# Master.net
KiCad netlist of a schematic drawn in Altium Designer
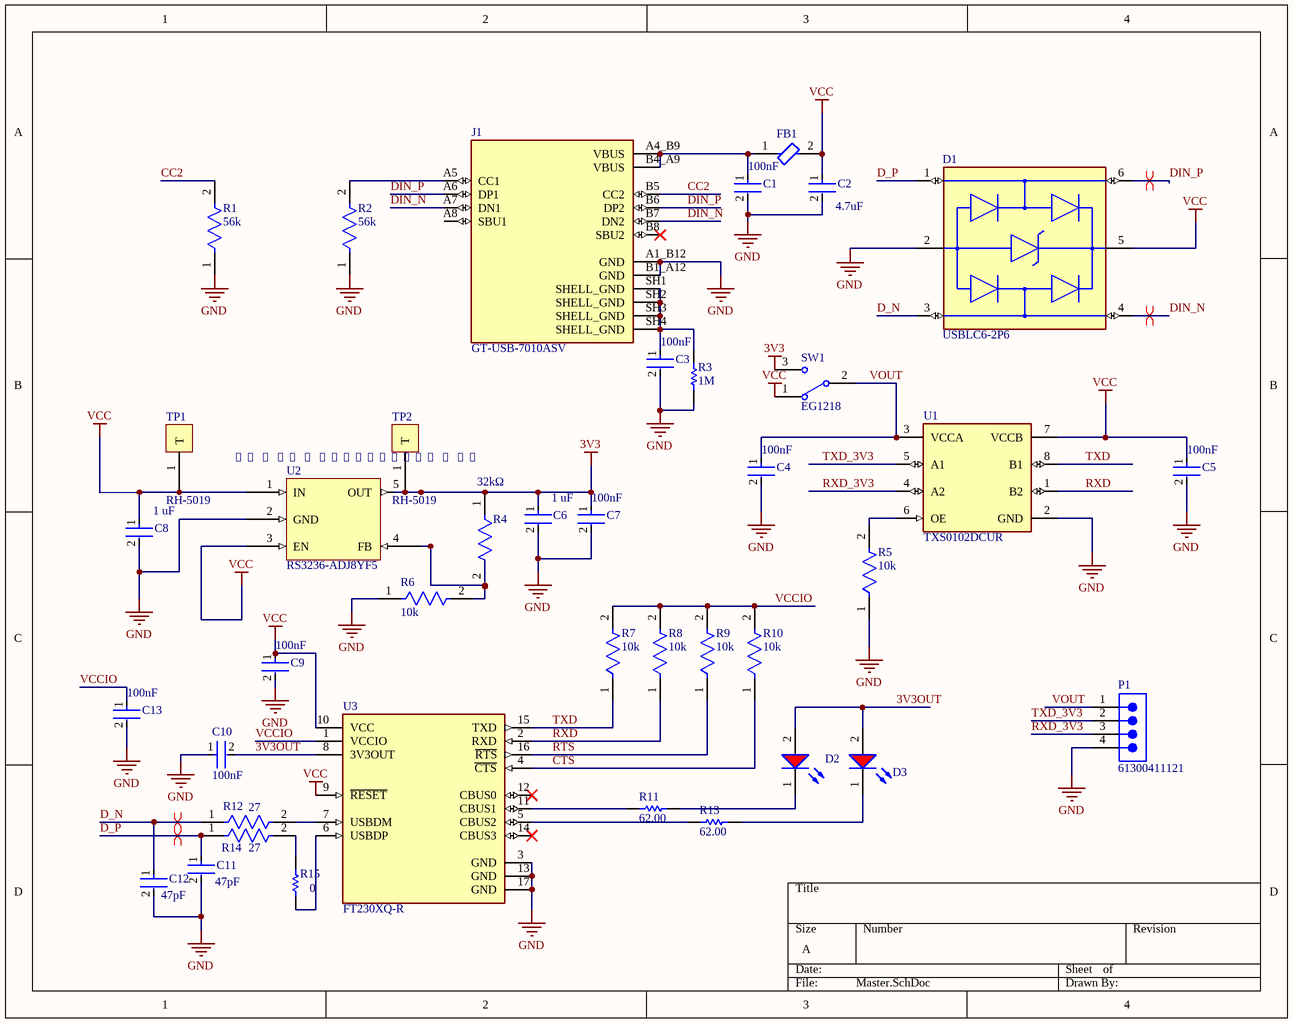
[diagram p0: Master.SchDoc]

(export (version "E")
  (design (tool "Eeschema 10.0.6"))
  (components
    (comp (ref "C1")
      (value "GRM155R71C104KA88J")
      (footprint "FP-GRM155-0_05-MFG")
      (fields
        (field (name "VOLTAGE") "16V")
        (field (name "TOLERANCE") "10%")
        (field (name "CAPACITANCE") "100nF")
      )
      (libsource (lib "Altium Content Vault") (part "b4654b650e69147ec39a6b967a45e02"))
    )
    (comp (ref "C2")
      (value "CL21A475KAQNNNE")
      (footprint "FP-CL21-IPC_A")
      (description "CL21 Series 0805 4.7uF 25V ±10% Tolerance X5R Multilayer Ceramic Chip Capacitor")
      (fields (field (name "CAPACITANCE") "4.7uF") (field (name "TOLERANCE") "10%"))
      (libsource (lib "Altium Content Vault") (part "b4654b650e69147ec39a6b967a45e02"))
    )
    (comp (ref "C3")
      (value "GRM155R71C104KA88J")
      (footprint "FP-GRM155-0_05-MFG")
      (fields
        (field (name "VOLTAGE") "16V")
        (field (name "TOLERANCE") "10%")
        (field (name "CAPACITANCE") "100nF")
      )
      (libsource (lib "Altium Content Vault") (part "b4654b650e69147ec39a6b967a45e02"))
    )
    (comp (ref "C4")
      (value "GRM155R71C104KA88J")
      (footprint "FP-GRM155-0_05-MFG")
      (fields
        (field (name "VOLTAGE") "16V")
        (field (name "TOLERANCE") "10%")
        (field (name "CAPACITANCE") "100nF")
      )
      (libsource (lib "Altium Content Vault") (part "b4654b650e69147ec39a6b967a45e02"))
    )
    (comp (ref "C5")
      (value "GRM155R71C104KA88J")
      (footprint "FP-GRM155-0_05-MFG")
      (fields
        (field (name "VOLTAGE") "16V")
        (field (name "TOLERANCE") "10%")
        (field (name "CAPACITANCE") "100nF")
      )
      (libsource (lib "Altium Content Vault") (part "b4654b650e69147ec39a6b967a45e02"))
    )
    (comp (ref "C6")
      (value "1 uF")
      (footprint "FP-CC0603-DA-MFG")
      (description "CAP CER 1UF 16V X7R 0603")
      (fields (field (name "TOLERANCE") "0.1") (field (name "MANUFACTURER") "YAGEO"))
      (libsource (lib "Altium Content Vault") (part "11868f565c42a9108669ba33697ecf6"))
    )
    (comp (ref "C7")
      (value "GRM155R71C104KA88J")
      (footprint "FP-GRM155-0_05-MFG")
      (fields
        (field (name "VOLTAGE") "16V")
        (field (name "TOLERANCE") "10%")
        (field (name "CAPACITANCE") "100nF")
      )
      (libsource (lib "Altium Content Vault") (part "b4654b650e69147ec39a6b967a45e02"))
    )
    (comp (ref "C8")
      (value "1 uF")
      (footprint "FP-CC0603-DA-MFG")
      (description "CAP CER 1UF 16V X7R 0603")
      (fields (field (name "TOLERANCE") "0.1") (field (name "MANUFACTURER") "YAGEO"))
      (libsource (lib "Altium Content Vault") (part "11868f565c42a9108669ba33697ecf6"))
    )
    (comp (ref "C9")
      (value "GRM155R71C104KA88J")
      (footprint "FP-GRM155-0_05-MFG")
      (fields
        (field (name "VOLTAGE") "16V")
        (field (name "TOLERANCE") "10%")
        (field (name "CAPACITANCE") "100nF")
      )
      (libsource (lib "Altium Content Vault") (part "b4654b650e69147ec39a6b967a45e02"))
    )
    (comp (ref "C10")
      (value "GRM155R71C104KA88J")
      (footprint "FP-GRM155-0_05-MFG")
      (fields
        (field (name "VOLTAGE") "16V")
        (field (name "TOLERANCE") "10%")
        (field (name "CAPACITANCE") "100nF")
      )
      (libsource (lib "Altium Content Vault") (part "b4654b650e69147ec39a6b967a45e02"))
    )
    (comp (ref "C11")
      (value "GJM1555C1H470GB01D")
      (footprint "FP-GJM155-0_05-IPC_A")
      (description "Multi-Layer Ceramic Capacitor 47pF C0G  ±2% 0402 Paper T/R")
      (fields (field (name "TOLERANCE") "2%") (field (name "CAPACITANCE") "47pF"))
      (libsource (lib "Altium Content Vault") (part "02cd4be3c70576c341d710602a673aa"))
    )
    (comp (ref "C12")
      (value "GJM1555C1H470GB01D")
      (footprint "FP-GJM155-0_05-IPC_A")
      (description "Multi-Layer Ceramic Capacitor 47pF C0G  ±2% 0402 Paper T/R")
      (fields (field (name "TOLERANCE") "2%") (field (name "CAPACITANCE") "47pF"))
      (libsource (lib "Altium Content Vault") (part "02cd4be3c70576c341d710602a673aa"))
    )
    (comp (ref "C13")
      (value "GRM155R71C104KA88J")
      (footprint "FP-GRM155-0_05-MFG")
      (fields
        (field (name "VOLTAGE") "16V")
        (field (name "TOLERANCE") "10%")
        (field (name "CAPACITANCE") "100nF")
      )
      (libsource (lib "Altium Content Vault") (part "b4654b650e69147ec39a6b967a45e02"))
    )
    (comp (ref "D1")
      (value "USBLC6-2P6")
      (footprint "FP-SOT-666-MFG")
      (description "TVS DIODE 5.25V 17V SOT666")
      (libsource (lib "Altium Content Vault") (part "c871e55f7e3243d341edbd671b98d92"))
    )
    (comp (ref "D2")
      (value "150080RS75000")
      (footprint "WL-SMCW_0805_150080xx75000")
      (description "LED Uni-Color Red 630nm 2-Pin Chip 0805(2012Metric) T/R")
      (libsource (lib "Altium Content Vault") (part "LED_Red_2A-1K"))
    )
    (comp (ref "D3")
      (value "150080RS75000")
      (footprint "WL-SMCW_0805_150080xx75000")
      (description "LED Uni-Color Red 630nm 2-Pin Chip 0805(2012Metric) T/R")
      (libsource (lib "Altium Content Vault") (part "LED_Red_2A-1K"))
    )
    (comp (ref "FB1")
      (value "BLM18PG600SN1D")
      (footprint "FP-BLM18-0_15-t0_8-IPC_B")
      (description "Chip Ferrite Bead, 0603, 60Ω @ 100MHz, 0.1Ω, , 1A")
      (fields (field (name "TOLERANCE") "25%"))
      (libsource (lib "Altium Content Vault") (part "5f30dd21d616792df468990f7003faa"))
    )
    (comp (ref "J1")
      (value "GT-USB-7010ASV")
      (footprint "GCT_USB4105-GF-A")
      (description "USB-C 2.0")
      (libsource (lib "Brian Tan") (part "USB4105-GF-A"))
    )
    (comp (ref "P1")
      (value "61300411121")
      (footprint "61300411121")
      (libsource (lib "Altium Content Vault") (part "Header_Male_1R_04P"))
    )
    (comp (ref "R1")
      (value "RMCF1206JT56K0")
      (footprint "FP-RMCF1206-MFG")
      (description "56kΩ ±5% 0.25W 1206 Thick Film Chip Resistor AEC-Q200 compliant")
      (fields (field (name "RESISTANCE") "56k") (field (name "TOLERANCE") "5%"))
      (libsource (lib "Altium Content Vault") (part "1029c3af85768c4190bb7ad29bc67b5"))
    )
    (comp (ref "R2")
      (value "RMCF1206JT56K0")
      (footprint "FP-RMCF1206-MFG")
      (description "56kΩ ±5% 0.25W 1206 Thick Film Chip Resistor AEC-Q200 compliant")
      (fields (field (name "RESISTANCE") "56k") (field (name "TOLERANCE") "5%"))
      (libsource (lib "Altium Content Vault") (part "1029c3af85768c4190bb7ad29bc67b5"))
    )
    (comp (ref "R3")
      (value "1M")
      (footprint "RESC1608X55X25LL10T15")
      (description "Chip Resistor, 1 MOhm, +/- 1%, 100 mW, -55 to 155 degC, 0603 (1608 Metric), RoHS, Tape and Reel")
      (fields (field (name "TOLERANCE") "20%"))
      (libsource (lib "Altium Content Vault") (part "RES-2"))
    )
    (comp (ref "R4")
      (value "RT0603BRD0732KL")
      (footprint "FP-RT0603-0_55-MFG")
      (description "RT0603BRD0732KL High Precision-High Stability Chip Resistor Thin Film 0603 32kOhm 0.1% Paper T/R")
      (fields (field (name "RESISTANCE") "32kΩ") (field (name "TOLERANCE") "0.1%"))
      (libsource (lib "Altium Content Vault") (part "1029c3af85768c4190bb7ad29bc67b5"))
    )
    (comp (ref "R5")
      (value "RC0603FR-0710KL")
      (footprint "FP-RC0603-0_55-IPC_C")
      (description "RES 10K OHM 1% 1/10W 0603")
      (fields (field (name "TOLERANCE") "1%") (field (name "RESISTANCE") "10k"))
      (libsource (lib "Altium Content Vault") (part "1029c3af85768c4190bb7ad29bc67b5"))
    )
    (comp (ref "R6")
      (value "RC0603FR-0710KL")
      (footprint "FP-RC0603-0_55-IPC_C")
      (description "RES 10K OHM 1% 1/10W 0603")
      (fields (field (name "TOLERANCE") "1%") (field (name "RESISTANCE") "10k"))
      (libsource (lib "Altium Content Vault") (part "1029c3af85768c4190bb7ad29bc67b5"))
    )
    (comp (ref "R7")
      (value "RC0603FR-0710KL")
      (footprint "FP-RC0603-0_55-IPC_C")
      (description "RES 10K OHM 1% 1/10W 0603")
      (fields (field (name "TOLERANCE") "1%") (field (name "RESISTANCE") "10k"))
      (libsource (lib "Altium Content Vault") (part "1029c3af85768c4190bb7ad29bc67b5"))
    )
    (comp (ref "R8")
      (value "RC0603FR-0710KL")
      (footprint "FP-RC0603-0_55-IPC_C")
      (description "RES 10K OHM 1% 1/10W 0603")
      (fields (field (name "TOLERANCE") "1%") (field (name "RESISTANCE") "10k"))
      (libsource (lib "Altium Content Vault") (part "1029c3af85768c4190bb7ad29bc67b5"))
    )
    (comp (ref "R9")
      (value "RC0603FR-0710KL")
      (footprint "FP-RC0603-0_55-IPC_C")
      (description "RES 10K OHM 1% 1/10W 0603")
      (fields (field (name "TOLERANCE") "1%") (field (name "RESISTANCE") "10k"))
      (libsource (lib "Altium Content Vault") (part "1029c3af85768c4190bb7ad29bc67b5"))
    )
    (comp (ref "R10")
      (value "RC0603FR-0710KL")
      (footprint "FP-RC0603-0_55-IPC_C")
      (description "RES 10K OHM 1% 1/10W 0603")
      (fields (field (name "TOLERANCE") "1%") (field (name "RESISTANCE") "10k"))
      (libsource (lib "Altium Content Vault") (part "1029c3af85768c4190bb7ad29bc67b5"))
    )
    (comp (ref "R11")
      (value "62.00")
      (footprint "RESC1206(3216)_N")
      (description "62R 0.25W 1% 1206 (3216 Metric)  SMD")
      (fields (field (name "POWER") "0.25 W") (field (name "TOLERANCE") "1 %"))
      (libsource (lib "Altium Content Vault") (part "RES"))
    )
    (comp (ref "R12")
      (value "ERJ-2RKF27R0X")
      (footprint "FP-ERJ2R-IPC_B")
      (description "RES SMD 27 OHM 1% 1/10W 0402")
      (fields (field (name "TOLERANCE") "1%") (field (name "RESISTANCE") "27"))
      (libsource (lib "Altium Content Vault") (part "8db39607336c341a927600551d01821"))
    )
    (comp (ref "R13")
      (value "62.00")
      (footprint "RESC1206(3216)_N")
      (description "62R 0.25W 1% 1206 (3216 Metric)  SMD")
      (fields (field (name "POWER") "0.25 W") (field (name "TOLERANCE") "1 %"))
      (libsource (lib "Altium Content Vault") (part "RES"))
    )
    (comp (ref "R14")
      (value "ERJ-2RKF27R0X")
      (footprint "FP-ERJ2R-IPC_B")
      (description "RES SMD 27 OHM 1% 1/10W 0402")
      (fields (field (name "TOLERANCE") "1%") (field (name "RESISTANCE") "27"))
      (libsource (lib "Altium Content Vault") (part "8db39607336c341a927600551d01821"))
    )
    (comp (ref "R15")
      (value "0")
      (footprint "RESC1005X40X25NL05T10")
      (fields (field (name "MANUFACTURER") "Yageo / Phycomp") (field (name "PART NUMBER") "RC0402JR-070RL"))
      (libsource (lib "Altium Content Vault") (part "RES"))
    )
    (comp (ref "SW1")
      (value "EG1218")
      (footprint "ESWI-EG1218_V")
      (description "Slide Switch, 500 V, -20 to 70 degC, 3-Pin THD, RoHS")
      (libsource (lib "Altium Content Vault") (part "SW-SPDT-3_B"))
    )
    (comp (ref "TP1")
      (value "RH-5019")
      (footprint "RH-5019-Footprint-1")
      (description "PC Test Point")
      (libsource (lib "Brian Tan") (part "RH-5019-Symbol-1"))
    )
    (comp (ref "TP2")
      (value "RH-5019")
      (footprint "RH-5019-Footprint-1")
      (description "PC Test Point")
      (libsource (lib "Brian Tan") (part "RH-5019-Symbol-1"))
    )
    (comp (ref "U1")
      (value "TXS0102DCUR")
      (footprint "FP-DCU0008A-MFG")
      (description "IC TRNSLTR BIDIRECTIONAL US8")
      (fields
        (field (name "MANUFACTURER") "Texas Instruments")
        (field (name "OCTOPART") "https://octopart.com/txs0102dcur-texas+instruments-5414308")
      )
      (libsource (lib "Altium Content Vault") (part "7edb3aeb21a89e92b7ef258fabac7d1"))
    )
    (comp (ref "U2")
      (value "RS3236-ADJ8YF5")
      (footprint "SOT95P245X110-5N")
      (description "IC Reg Lin Pos Adj 500MA SOT23-5")
      (libsource (lib "Brian Tan") (part "RS3236-ADJ8YF5-Symbol-1"))
    )
    (comp (ref "U3")
      (value "FT230XQ-R")
      (footprint "FP-QFN-16-MFG")
      (description "IC USB SERIAL BASIC UART 16QFN")
      (libsource (lib "Altium Content Vault") (part "29d2eb9587eff32afae5da052de4085"))
    )
  )
  (nets
    (net (code "1") (name "/3V3OUT") (class "Default")
      (node (ref "C10") (pin "2") (pinfunction "2_2") (pintype "passive"))
      (node (ref "D2") (pin "2") (pinfunction "A_2") (pintype "passive"))
      (node (ref "D3") (pin "2") (pinfunction "A_2") (pintype "passive"))
      (node (ref "U3") (pin "8") (pinfunction "3V3OUT_8") (pintype "power_in"))
    )
    (net (code "2") (name "/CC2") (class "Default")
      (node (ref "J1") (pin "B5") (pinfunction "CC2_B5") (pintype "bidirectional"))
      (node (ref "R1") (pin "2") (pinfunction "2_2") (pintype "passive"))
    )
    (net (code "3") (name "/CTS") (class "Default")
      (node (ref "R10") (pin "1") (pinfunction "1_1") (pintype "passive"))
      (node (ref "U3") (pin "4") (pinfunction "~{CTS}_4") (pintype "input"))
    )
    (net (code "4") (name "/DIN_N") (class "Default")
      (node (ref "D1") (pin "4") (pinfunction "I/O2_4") (pintype "bidirectional"))
      (node (ref "J1") (pin "A7") (pinfunction "DN1_A7") (pintype "bidirectional"))
      (node (ref "J1") (pin "B7") (pinfunction "DN2_B7") (pintype "bidirectional"))
    )
    (net (code "5") (name "/DIN_P") (class "Default")
      (node (ref "D1") (pin "6") (pinfunction "I/O1_6") (pintype "bidirectional"))
      (node (ref "J1") (pin "A6") (pinfunction "DP1_A6") (pintype "bidirectional"))
      (node (ref "J1") (pin "B6") (pinfunction "DP2_B6") (pintype "bidirectional"))
    )
    (net (code "6") (name "/D_N") (class "Default")
      (node (ref "C12") (pin "1") (pinfunction "1_1") (pintype "passive"))
      (node (ref "D1") (pin "3") (pinfunction "I/O2_3") (pintype "bidirectional"))
      (node (ref "R12") (pin "1") (pinfunction "1_1") (pintype "passive"))
    )
    (net (code "7") (name "/D_P") (class "Default")
      (node (ref "C11") (pin "1") (pinfunction "1_1") (pintype "passive"))
      (node (ref "D1") (pin "1") (pinfunction "I/O1_1") (pintype "bidirectional"))
      (node (ref "R14") (pin "1") (pinfunction "1_1") (pintype "passive"))
    )
    (net (code "8") (name "/RTS") (class "Default")
      (node (ref "R9") (pin "1") (pinfunction "1_1") (pintype "passive"))
      (node (ref "U3") (pin "16") (pinfunction "~{RTS}_16") (pintype "output"))
    )
    (net (code "9") (name "/RXD") (class "Default")
      (node (ref "R8") (pin "1") (pinfunction "1_1") (pintype "passive"))
      (node (ref "U1") (pin "1") (pinfunction "B2_1") (pintype "bidirectional"))
      (node (ref "U3") (pin "2") (pinfunction "RXD_2") (pintype "input"))
    )
    (net (code "10") (name "/RXD_3V3") (class "Default")
      (node (ref "P1") (pin "3") (pinfunction "3_3") (pintype "passive"))
      (node (ref "U1") (pin "4") (pinfunction "A2_4") (pintype "bidirectional"))
    )
    (net (code "11") (name "/TXD") (class "Default")
      (node (ref "R7") (pin "1") (pinfunction "1_1") (pintype "passive"))
      (node (ref "U1") (pin "8") (pinfunction "B1_8") (pintype "bidirectional"))
      (node (ref "U3") (pin "15") (pinfunction "TXD_15") (pintype "output"))
    )
    (net (code "12") (name "/TXD_3V3") (class "Default")
      (node (ref "P1") (pin "2") (pinfunction "2_2") (pintype "passive"))
      (node (ref "U1") (pin "5") (pinfunction "A1_5") (pintype "bidirectional"))
    )
    (net (code "13") (name "/VCCIO") (class "Default")
      (node (ref "C13") (pin "1") (pinfunction "1_1") (pintype "passive"))
      (node (ref "R10") (pin "2") (pinfunction "2_2") (pintype "passive"))
      (node (ref "R7") (pin "2") (pinfunction "2_2") (pintype "passive"))
      (node (ref "R8") (pin "2") (pinfunction "2_2") (pintype "passive"))
      (node (ref "R9") (pin "2") (pinfunction "2_2") (pintype "passive"))
      (node (ref "U3") (pin "1") (pinfunction "VCCIO_1") (pintype "power_in"))
    )
    (net (code "14") (name "/VOUT") (class "Default")
      (node (ref "C4") (pin "1") (pinfunction "1_1") (pintype "passive"))
      (node (ref "P1") (pin "1") (pinfunction "1_1") (pintype "passive"))
      (node (ref "SW1") (pin "2") (pinfunction "COM_2") (pintype "passive"))
      (node (ref "U1") (pin "3") (pinfunction "VCCA_3") (pintype "power_in"))
    )
    (net (code "15") (name "3V3") (class "Default")
      (node (ref "C6") (pin "1") (pinfunction "1_1") (pintype "passive"))
      (node (ref "C7") (pin "1") (pinfunction "1_1") (pintype "passive"))
      (node (ref "R4") (pin "1") (pinfunction "1_1") (pintype "passive"))
      (node (ref "SW1") (pin "3") (pinfunction "3_3") (pintype "passive"))
      (node (ref "TP2") (pin "1") (pinfunction "T_1") (pintype "passive"))
      (node (ref "U2") (pin "5") (pinfunction "OUT_5") (pintype "output"))
    )
    (net (code "16") (name "GND") (class "Default")
      (node (ref "C1") (pin "2") (pinfunction "2_2") (pintype "passive"))
      (node (ref "C10") (pin "1") (pinfunction "1_1") (pintype "passive"))
      (node (ref "C11") (pin "2") (pinfunction "2_2") (pintype "passive"))
      (node (ref "C12") (pin "2") (pinfunction "2_2") (pintype "passive"))
      (node (ref "C13") (pin "2") (pinfunction "2_2") (pintype "passive"))
      (node (ref "C2") (pin "2") (pinfunction "2_2") (pintype "passive"))
      (node (ref "C3") (pin "2") (pinfunction "2_2") (pintype "passive"))
      (node (ref "C4") (pin "2") (pinfunction "2_2") (pintype "passive"))
      (node (ref "C5") (pin "2") (pinfunction "2_2") (pintype "passive"))
      (node (ref "C6") (pin "2") (pinfunction "2_2") (pintype "passive"))
      (node (ref "C7") (pin "2") (pinfunction "2_2") (pintype "passive"))
      (node (ref "C8") (pin "2") (pinfunction "2_2") (pintype "passive"))
      (node (ref "C9") (pin "2") (pinfunction "2_2") (pintype "passive"))
      (node (ref "D1") (pin "2") (pinfunction "GND_2") (pintype "power_in"))
      (node (ref "J1") (pin "A1_B12") (pinfunction "GND_A1_B12") (pintype "power_in"))
      (node (ref "J1") (pin "B1_A12") (pinfunction "GND_B1_A12") (pintype "power_in"))
      (node (ref "P1") (pin "4") (pinfunction "4_4") (pintype "passive"))
      (node (ref "R1") (pin "1") (pinfunction "1_1") (pintype "passive"))
      (node (ref "R2") (pin "1") (pinfunction "1_1") (pintype "passive"))
      (node (ref "R3") (pin "2") (pinfunction "2_2") (pintype "passive"))
      (node (ref "R5") (pin "1") (pinfunction "1_1") (pintype "passive"))
      (node (ref "R6") (pin "1") (pinfunction "1_1") (pintype "passive"))
      (node (ref "U1") (pin "2") (pinfunction "GND_2") (pintype "power_in"))
      (node (ref "U2") (pin "2") (pinfunction "GND_2") (pintype "input"))
      (node (ref "U3") (pin "13") (pinfunction "GND_13") (pintype "power_in"))
      (node (ref "U3") (pin "17") (pinfunction "GND_17") (pintype "power_in"))
      (node (ref "U3") (pin "3") (pinfunction "GND_3") (pintype "power_in"))
    )
    (net (code "17") (name "Net-(C1-Pad1)") (class "Default")
      (node (ref "C1") (pin "1") (pinfunction "1_1") (pintype "passive"))
      (node (ref "FB1") (pin "1") (pinfunction "1_1") (pintype "passive"))
      (node (ref "J1") (pin "A4_B9") (pinfunction "VBUS_A4_B9") (pintype "power_in"))
      (node (ref "J1") (pin "B4_A9") (pinfunction "VBUS_B4_A9") (pintype "power_in"))
    )
    (net (code "18") (name "Net-(C3-Pad1)") (class "Default")
      (node (ref "C3") (pin "1") (pinfunction "1_1") (pintype "passive"))
      (node (ref "J1") (pin "SH1") (pinfunction "SHELL_GND_SH1") (pintype "power_in"))
      (node (ref "J1") (pin "SH2") (pinfunction "SHELL_GND_SH2") (pintype "power_in"))
      (node (ref "J1") (pin "SH3") (pinfunction "SHELL_GND_SH3") (pintype "power_in"))
      (node (ref "J1") (pin "SH4") (pinfunction "SHELL_GND_SH4") (pintype "power_in"))
      (node (ref "R3") (pin "1") (pinfunction "1_1") (pintype "passive"))
    )
    (net (code "19") (name "Net-(D2-K)") (class "Default")
      (node (ref "D2") (pin "1") (pinfunction "K_1") (pintype "passive"))
      (node (ref "R11") (pin "1") (pinfunction "1_1") (pintype "passive"))
    )
    (net (code "20") (name "Net-(D3-K)") (class "Default")
      (node (ref "D3") (pin "1") (pinfunction "K_1") (pintype "passive"))
      (node (ref "R13") (pin "1") (pinfunction "1_1") (pintype "passive"))
    )
    (net (code "21") (name "Net-(J1-CC1)") (class "Default")
      (node (ref "J1") (pin "A5") (pinfunction "CC1_A5") (pintype "bidirectional"))
      (node (ref "R2") (pin "2") (pinfunction "2_2") (pintype "passive"))
    )
    (net (code "22") (name "Net-(R14-Pad2)") (class "Default")
      (node (ref "R14") (pin "2") (pinfunction "2_2") (pintype "passive"))
      (node (ref "R15") (pin "2") (pinfunction "2_2") (pintype "passive"))
    )
    (net (code "23") (name "Net-(U1-OE)") (class "Default")
      (node (ref "R5") (pin "2") (pinfunction "2_2") (pintype "passive"))
      (node (ref "U1") (pin "6") (pinfunction "OE_6") (pintype "input"))
    )
    (net (code "24") (name "Net-(U2-FB)") (class "Default")
      (node (ref "R4") (pin "2") (pinfunction "2_2") (pintype "passive"))
      (node (ref "R6") (pin "2") (pinfunction "2_2") (pintype "passive"))
      (node (ref "U2") (pin "4") (pinfunction "FB_4") (pintype "input"))
    )
    (net (code "25") (name "Net-(U3-CBUS1)") (class "Default")
      (node (ref "R11") (pin "2") (pinfunction "2_2") (pintype "passive"))
      (node (ref "U3") (pin "11") (pinfunction "CBUS1_11") (pintype "bidirectional"))
    )
    (net (code "26") (name "Net-(U3-CBUS2)") (class "Default")
      (node (ref "R13") (pin "2") (pinfunction "2_2") (pintype "passive"))
      (node (ref "U3") (pin "5") (pinfunction "CBUS2_5") (pintype "bidirectional"))
    )
    (net (code "27") (name "Net-(U3-USBDM)") (class "Default")
      (node (ref "R12") (pin "2") (pinfunction "2_2") (pintype "passive"))
      (node (ref "U3") (pin "7") (pinfunction "USBDM_7") (pintype "input"))
    )
    (net (code "28") (name "Net-(U3-USBDP)") (class "Default")
      (node (ref "R15") (pin "1") (pinfunction "1_1") (pintype "passive"))
      (node (ref "U3") (pin "6") (pinfunction "USBDP_6") (pintype "input"))
    )
    (net (code "29") (name "VCC") (class "Default")
      (node (ref "C2") (pin "1") (pinfunction "1_1") (pintype "passive"))
      (node (ref "C5") (pin "1") (pinfunction "1_1") (pintype "passive"))
      (node (ref "C8") (pin "1") (pinfunction "1_1") (pintype "passive"))
      (node (ref "C9") (pin "1") (pinfunction "1_1") (pintype "passive"))
      (node (ref "D1") (pin "5") (pinfunction "VBUS_5") (pintype "power_in"))
      (node (ref "FB1") (pin "2") (pinfunction "2_2") (pintype "passive"))
      (node (ref "SW1") (pin "1") (pinfunction "1_1") (pintype "passive"))
      (node (ref "TP1") (pin "1") (pinfunction "T_1") (pintype "passive"))
      (node (ref "U1") (pin "7") (pinfunction "VCCB_7") (pintype "power_in"))
      (node (ref "U2") (pin "1") (pinfunction "IN_1") (pintype "input"))
      (node (ref "U2") (pin "3") (pinfunction "EN_3") (pintype "input"))
      (node (ref "U3") (pin "10") (pinfunction "VCC_10") (pintype "power_in"))
      (node (ref "U3") (pin "9") (pinfunction "~{RESET}_9") (pintype "input"))
    )
    (net (code "30") (name "unconnected-(J1-SBU1-PadA8)") (class "Default")
      (node (ref "J1") (pin "A8") (pinfunction "SBU1_A8") (pintype "bidirectional"))
    )
    (net (code "31") (name "unconnected-(J1-SBU2-PadB8)") (class "Default")
      (node (ref "J1") (pin "B8") (pinfunction "SBU2_B8") (pintype "bidirectional+no_connect"))
    )
    (net (code "32") (name "unconnected-(U3-CBUS0-Pad12)") (class "Default")
      (node (ref "U3") (pin "12") (pinfunction "CBUS0_12") (pintype "bidirectional+no_connect"))
    )
    (net (code "33") (name "unconnected-(U3-CBUS3-Pad14)") (class "Default")
      (node (ref "U3") (pin "14") (pinfunction "CBUS3_14") (pintype "bidirectional+no_connect"))
    )
  )
)
